# USB.net
KiCad netlist of a schematic drawn in Altium Designer
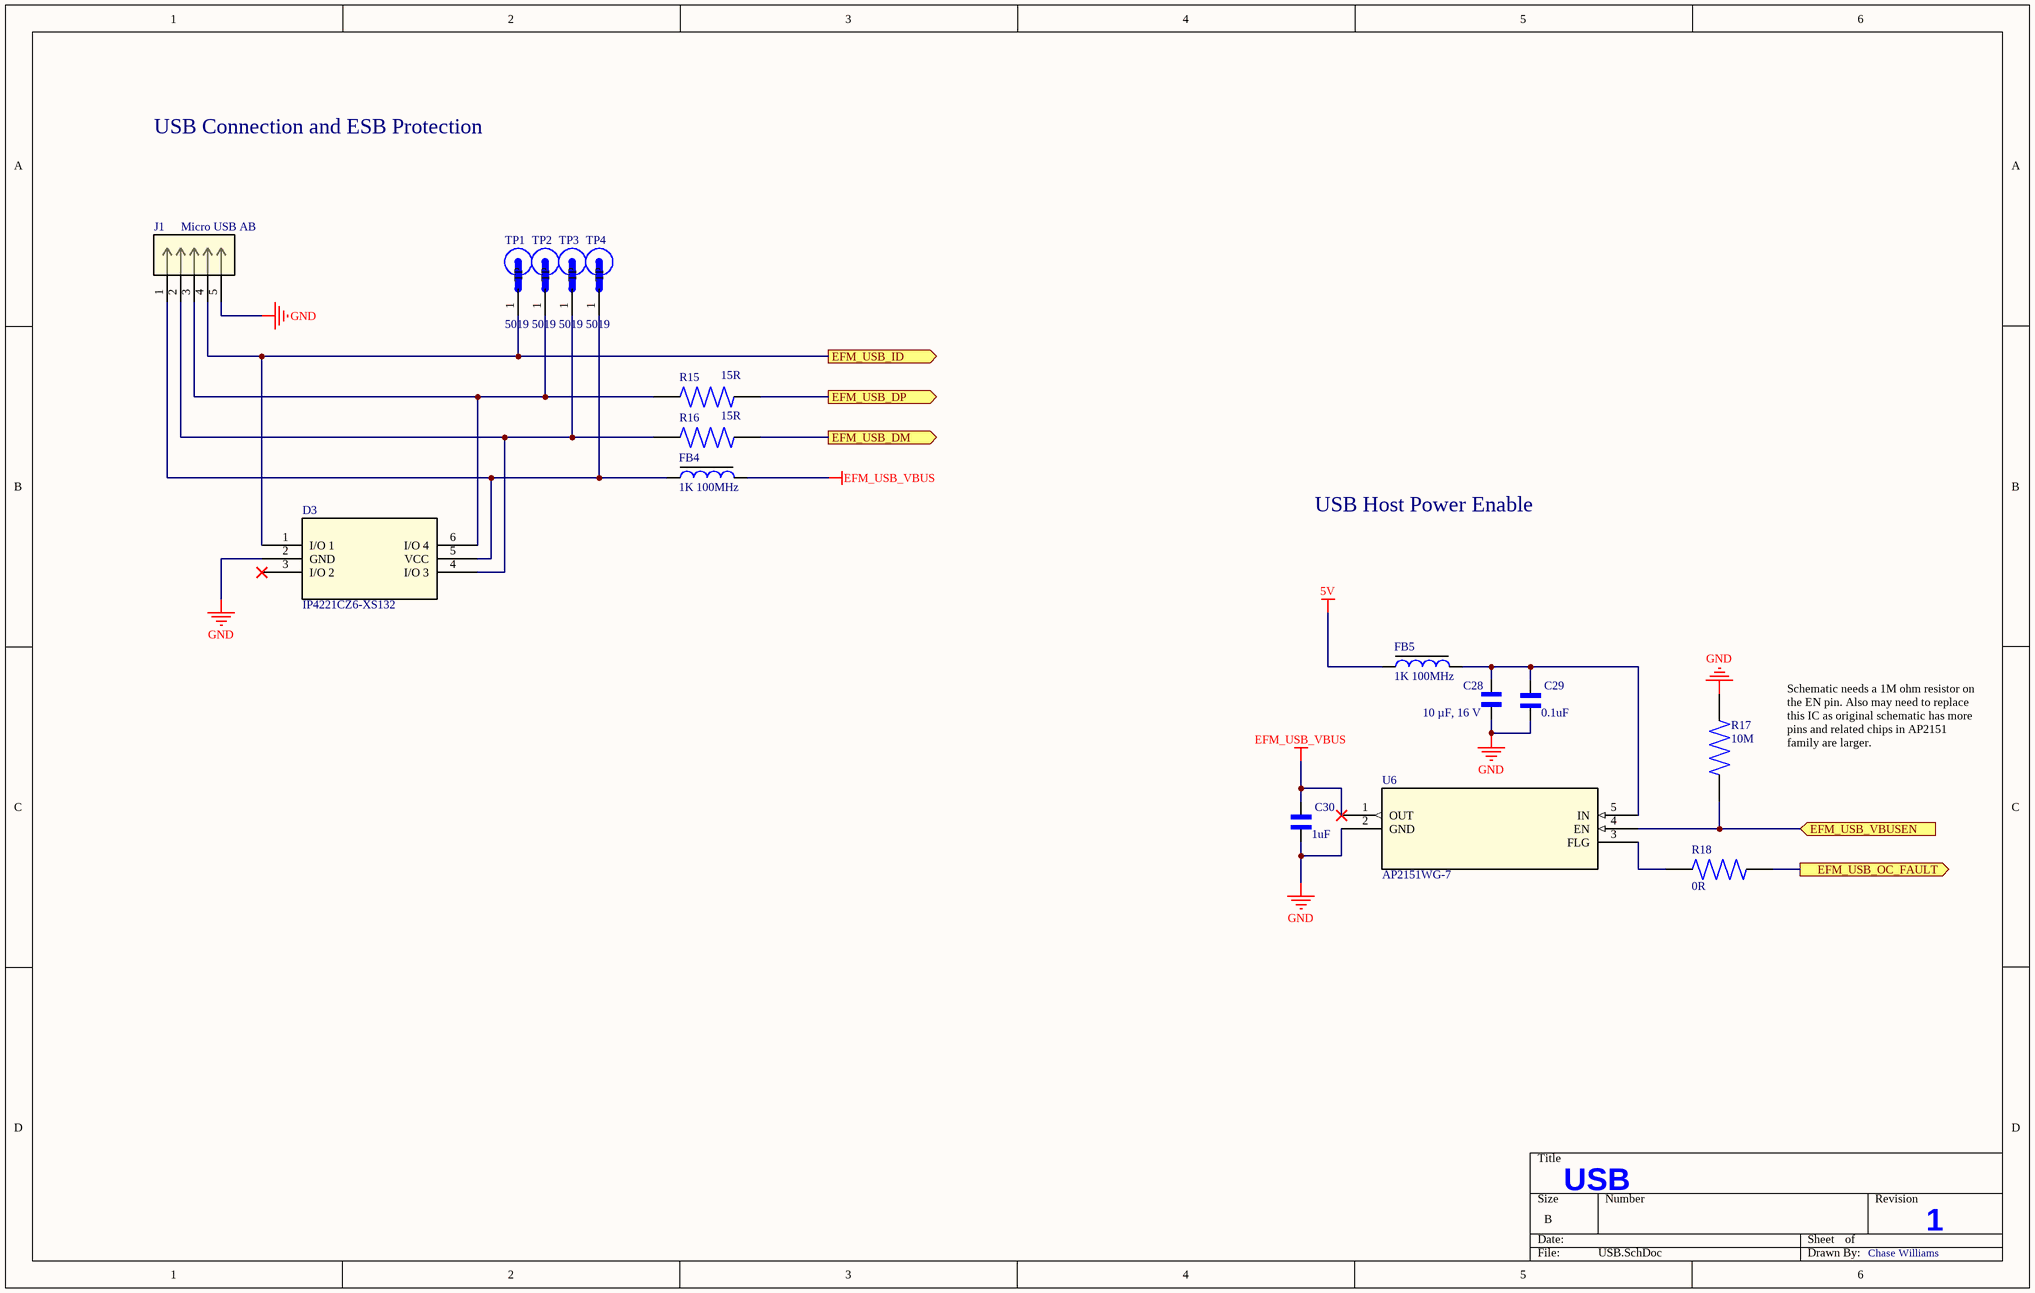
[diagram p0: USB.SchDoc]

(export (version "E")
  (design (tool "Eeschema 10.0.6"))
  (components
    (comp (ref "C28")
      (value "10 µF, 16 V")
      (footprint "C0805")
      (fields
        (field (name "MANUFACTURER") "TDK")
        (field (name "MANUFACTURER PART NUMBER") "C2012X5R1C106K085AC")
        (field (name "TOLERANCE") "10%")
      )
      (libsource (lib "nnts") (part "C2012X5R1C106K085AC"))
    )
    (comp (ref "C29")
      (value "0.1uF")
      (footprint "C0402")
      (description "CAP CER 0.1UF 6.3V X5R 01005")
      (fields
        (field (name "MANUFACTURER") "Murata")
        (field (name "MANUFACTURER PART NUMBER") "GRM022R60J104KE15L")
      )
      (libsource (lib "nnts") (part "GRM022R60J104KE15L"))
    )
    (comp (ref "C30")
      (value "1uF")
      (footprint "C0603")
      (description "SAMSUNG ELECTRO-MECHANICS - CL10A105KO8NNNC - CAP, 1UF, 16V, MLCC, 0603")
      (fields
        (field (name "MANUFACTURER") "Samsung")
        (field (name "MANUFACTURER PART NUMBER") "CL10A105KO8NNNC")
      )
      (libsource (lib "nnts") (part "CL10A105KO8NNNC"))
    )
    (comp (ref "D3")
      (value "IP4221CZ6-XS132")
      (footprint "SOT886_NEX-M")
      (description "TVS DIODE 5.5VWM SOT891")
      (fields (field (name "MANUFACTURER") "NXP Semiconductors"))
      (libsource (lib "nnts") (part "IP4221CZ6-XS132"))
    )
    (comp (ref "FB4")
      (value "1K 100MHz")
      (footprint "FB0603")
      (description "Ferrite Beads Multi-Layer Chip Bead 1KOhm 25% 100MHz 600mA 0603 T/R")
      (fields
        (field (name "MANUFACTURER") "Wurth Electronics")
        (field (name "MANUFACTURER PART NUMBER") "742792662")
      )
      (libsource (lib "nnts") (part "742792662"))
    )
    (comp (ref "FB5")
      (value "1K 100MHz")
      (footprint "FB0603")
      (description "Ferrite Beads Multi-Layer Chip Bead 1KOhm 25% 100MHz 600mA 0603 T/R")
      (fields
        (field (name "MANUFACTURER") "Wurth Electronics")
        (field (name "MANUFACTURER PART NUMBER") "742792662")
      )
      (libsource (lib "nnts") (part "742792662"))
    )
    (comp (ref "J1")
      (value "Micro USB AB")
      (footprint "Molex Micro USB")
      (description "https://www.molex.com/molex/products/part-detail/io_connectors/0475890001")
      (fields
        (field (name "MANUFACTURER_PART_NUMBER") "47589-0001")
        (field (name "COPYRIGHT") "Copyright (C) 2016 Accelerated Designs. All rights reserved")
      )
      (libsource (lib "nnts") (part "Molex Micro USB"))
    )
    (comp (ref "R15")
      (value "15R")
      (footprint "R0402 Vishay")
      (fields
        (field (name "MANUFACTURER") "Vishay")
        (field (name "MANUFACTURER PART NUMBER") "CRCW040215R0FKED")
        (field (name "TOLERANCE") "1%")
      )
      (libsource (lib "nnts") (part "CRCW040215R0FKED"))
    )
    (comp (ref "R16")
      (value "15R")
      (footprint "R0402 Vishay")
      (fields
        (field (name "MANUFACTURER") "Vishay")
        (field (name "MANUFACTURER PART NUMBER") "CRCW040215R0FKED")
        (field (name "TOLERANCE") "1%")
      )
      (libsource (lib "nnts") (part "CRCW040215R0FKED"))
    )
    (comp (ref "R17")
      (value "10M")
      (footprint "R0402 Vishay")
      (fields
        (field (name "MANUFACTURER") "Vishay")
        (field (name "MANUFACTURER PART NUMBER") "CRCW040210M0FKED")
        (field (name "TOLERANCE") "1%")
      )
      (libsource (lib "nnts") (part "CRCW040210M0FKED"))
    )
    (comp (ref "R18")
      (value "0R")
      (footprint "R0805 Yageo")
      (description "Surface Mount Thick Film Resistor, RC Series, 125 mW, - 5%, 150 V, 0805 [2012 Metric]")
      (fields
        (field (name "MANUFACTURER") "Yageo")
        (field (name "MANUFACTURER PART NUMBER") "RC0805JR-070RL")
      )
      (libsource (lib "nnts") (part "RC0805JR-070RL"))
    )
    (comp (ref "TP1")
      (value "5019")
      (footprint "TP380X203")
      (description "PC Test Point, Miniature Phosphor Bronze, Silver Plating Surface Mount Mounting Type")
      (fields (field (name "MF") "Keystone Electronics") (field (name "DIGI-KEY_PART_NUMBER") "36-5019CT-ND"))
      (libsource (lib "nnts") (part "5019"))
    )
    (comp (ref "TP2")
      (value "5019")
      (footprint "TP380X203")
      (description "PC Test Point, Miniature Phosphor Bronze, Silver Plating Surface Mount Mounting Type")
      (fields (field (name "MF") "Keystone Electronics") (field (name "DIGI-KEY_PART_NUMBER") "36-5019CT-ND"))
      (libsource (lib "nnts") (part "5019"))
    )
    (comp (ref "TP3")
      (value "5019")
      (footprint "TP380X203")
      (description "PC Test Point, Miniature Phosphor Bronze, Silver Plating Surface Mount Mounting Type")
      (fields (field (name "MF") "Keystone Electronics") (field (name "DIGI-KEY_PART_NUMBER") "36-5019CT-ND"))
      (libsource (lib "nnts") (part "5019"))
    )
    (comp (ref "TP4")
      (value "5019")
      (footprint "TP380X203")
      (description "PC Test Point, Miniature Phosphor Bronze, Silver Plating Surface Mount Mounting Type")
      (fields (field (name "MF") "Keystone Electronics") (field (name "DIGI-KEY_PART_NUMBER") "36-5019CT-ND"))
      (libsource (lib "nnts") (part "5019"))
    )
    (comp (ref "U6")
      (value "AP2151WG-7")
      (footprint "AP2151FMG-7")
      (description "U400")
      (fields (field (name "COPYRIGHT") "Copyright (C) 2018 Accelerated Designs. All rights reserved"))
      (libsource (lib "nnts") (part "AP2151WG-7"))
    )
  )
  (nets
    (net (code "2") (name "/EFM_USB_DM") (class "Default")
      (node (ref "R16") (pin "2") (pinfunction "2_2") (pintype "passive"))
    )
    (net (code "3") (name "/EFM_USB_DP") (class "Default")
      (node (ref "R15") (pin "2") (pinfunction "2_2") (pintype "passive"))
    )
    (net (code "4") (name "/EFM_USB_ID") (class "Default")
      (node (ref "D3") (pin "1") (pinfunction "I/O_1_1") (pintype "passive"))
      (node (ref "J1") (pin "4") (pinfunction "ID_4") (pintype "passive"))
      (node (ref "TP1") (pin "1") (pinfunction "TP_1") (pintype "passive"))
    )
    (net (code "5") (name "/EFM_USB_OC_FAULT") (class "Default")
      (node (ref "R18") (pin "2") (pinfunction "2_2") (pintype "passive"))
    )
    (net (code "6") (name "/EFM_USB_VBUSEN") (class "Default")
      (node (ref "R17") (pin "1") (pinfunction "1_1") (pintype "passive"))
      (node (ref "U6") (pin "4") (pinfunction "EN_4") (pintype "input"))
    )
    (net (code "7") (name "5V") (class "Default")
      (node (ref "FB5") (pin "1") (pinfunction "1_1") (pintype "passive"))
    )
    (net (code "8") (name "EFM_USB_VBUS") (class "Default")
      (node (ref "C30") (pin "2") (pinfunction "2_2") (pintype "passive"))
      (node (ref "FB4") (pin "2") (pinfunction "2_2") (pintype "passive"))
      (node (ref "U6") (pin "1") (pinfunction "OUT_1") (pintype "output"))
    )
    (net (code "9") (name "GND") (class "Default")
      (node (ref "C28") (pin "2") (pinfunction "2_2") (pintype "passive"))
      (node (ref "C29") (pin "1") (pinfunction "1_1") (pintype "passive"))
      (node (ref "C30") (pin "1") (pinfunction "1_1") (pintype "passive"))
      (node (ref "D3") (pin "2") (pinfunction "GND_2") (pintype "passive"))
      (node (ref "J1") (pin "5") (pinfunction "GND_5") (pintype "passive"))
      (node (ref "R17") (pin "2") (pinfunction "2_2") (pintype "passive"))
      (node (ref "U6") (pin "2") (pinfunction "GND_2") (pintype "power_in"))
    )
    (net (code "10") (name "Net-(D3-I{slash}O_3)") (class "Default")
      (node (ref "D3") (pin "4") (pinfunction "I/O_3_4") (pintype "passive"))
      (node (ref "J1") (pin "2") (pinfunction "D-_2") (pintype "passive"))
      (node (ref "R16") (pin "1") (pinfunction "1_1") (pintype "passive"))
      (node (ref "TP3") (pin "1") (pinfunction "TP_1") (pintype "passive"))
    )
    (net (code "11") (name "Net-(D3-I{slash}O_4)") (class "Default")
      (node (ref "D3") (pin "6") (pinfunction "I/O_4_6") (pintype "passive"))
      (node (ref "J1") (pin "3") (pinfunction "D+_3") (pintype "passive"))
      (node (ref "R15") (pin "1") (pinfunction "1_1") (pintype "passive"))
      (node (ref "TP2") (pin "1") (pinfunction "TP_1") (pintype "passive"))
    )
    (net (code "12") (name "Net-(D3-VCC)") (class "Default")
      (node (ref "D3") (pin "5") (pinfunction "VCC_5") (pintype "passive"))
      (node (ref "FB4") (pin "1") (pinfunction "1_1") (pintype "passive"))
      (node (ref "J1") (pin "1") (pinfunction "VBUS_1") (pintype "passive"))
      (node (ref "TP4") (pin "1") (pinfunction "TP_1") (pintype "passive"))
    )
    (net (code "13") (name "Net-(U6-FLG)") (class "Default")
      (node (ref "R18") (pin "1") (pinfunction "1_1") (pintype "passive"))
      (node (ref "U6") (pin "3") (pinfunction "FLG_3") (pintype "passive"))
    )
    (net (code "14") (name "Net-(U6-IN)") (class "Default")
      (node (ref "C28") (pin "1") (pinfunction "1_1") (pintype "passive"))
      (node (ref "C29") (pin "2") (pinfunction "2_2") (pintype "passive"))
      (node (ref "FB5") (pin "2") (pinfunction "2_2") (pintype "passive"))
      (node (ref "U6") (pin "5") (pinfunction "IN_5") (pintype "input"))
    )
    (net (code "15") (name "unconnected-(D3-I{slash}O_2-Pad3)") (class "Default")
      (node (ref "D3") (pin "3") (pinfunction "I/O_2_3") (pintype "passive+no_connect"))
    )
  )
)
